# cryptostick-0v3.net
KiCad netlist of a schematic drawn in EAGLE
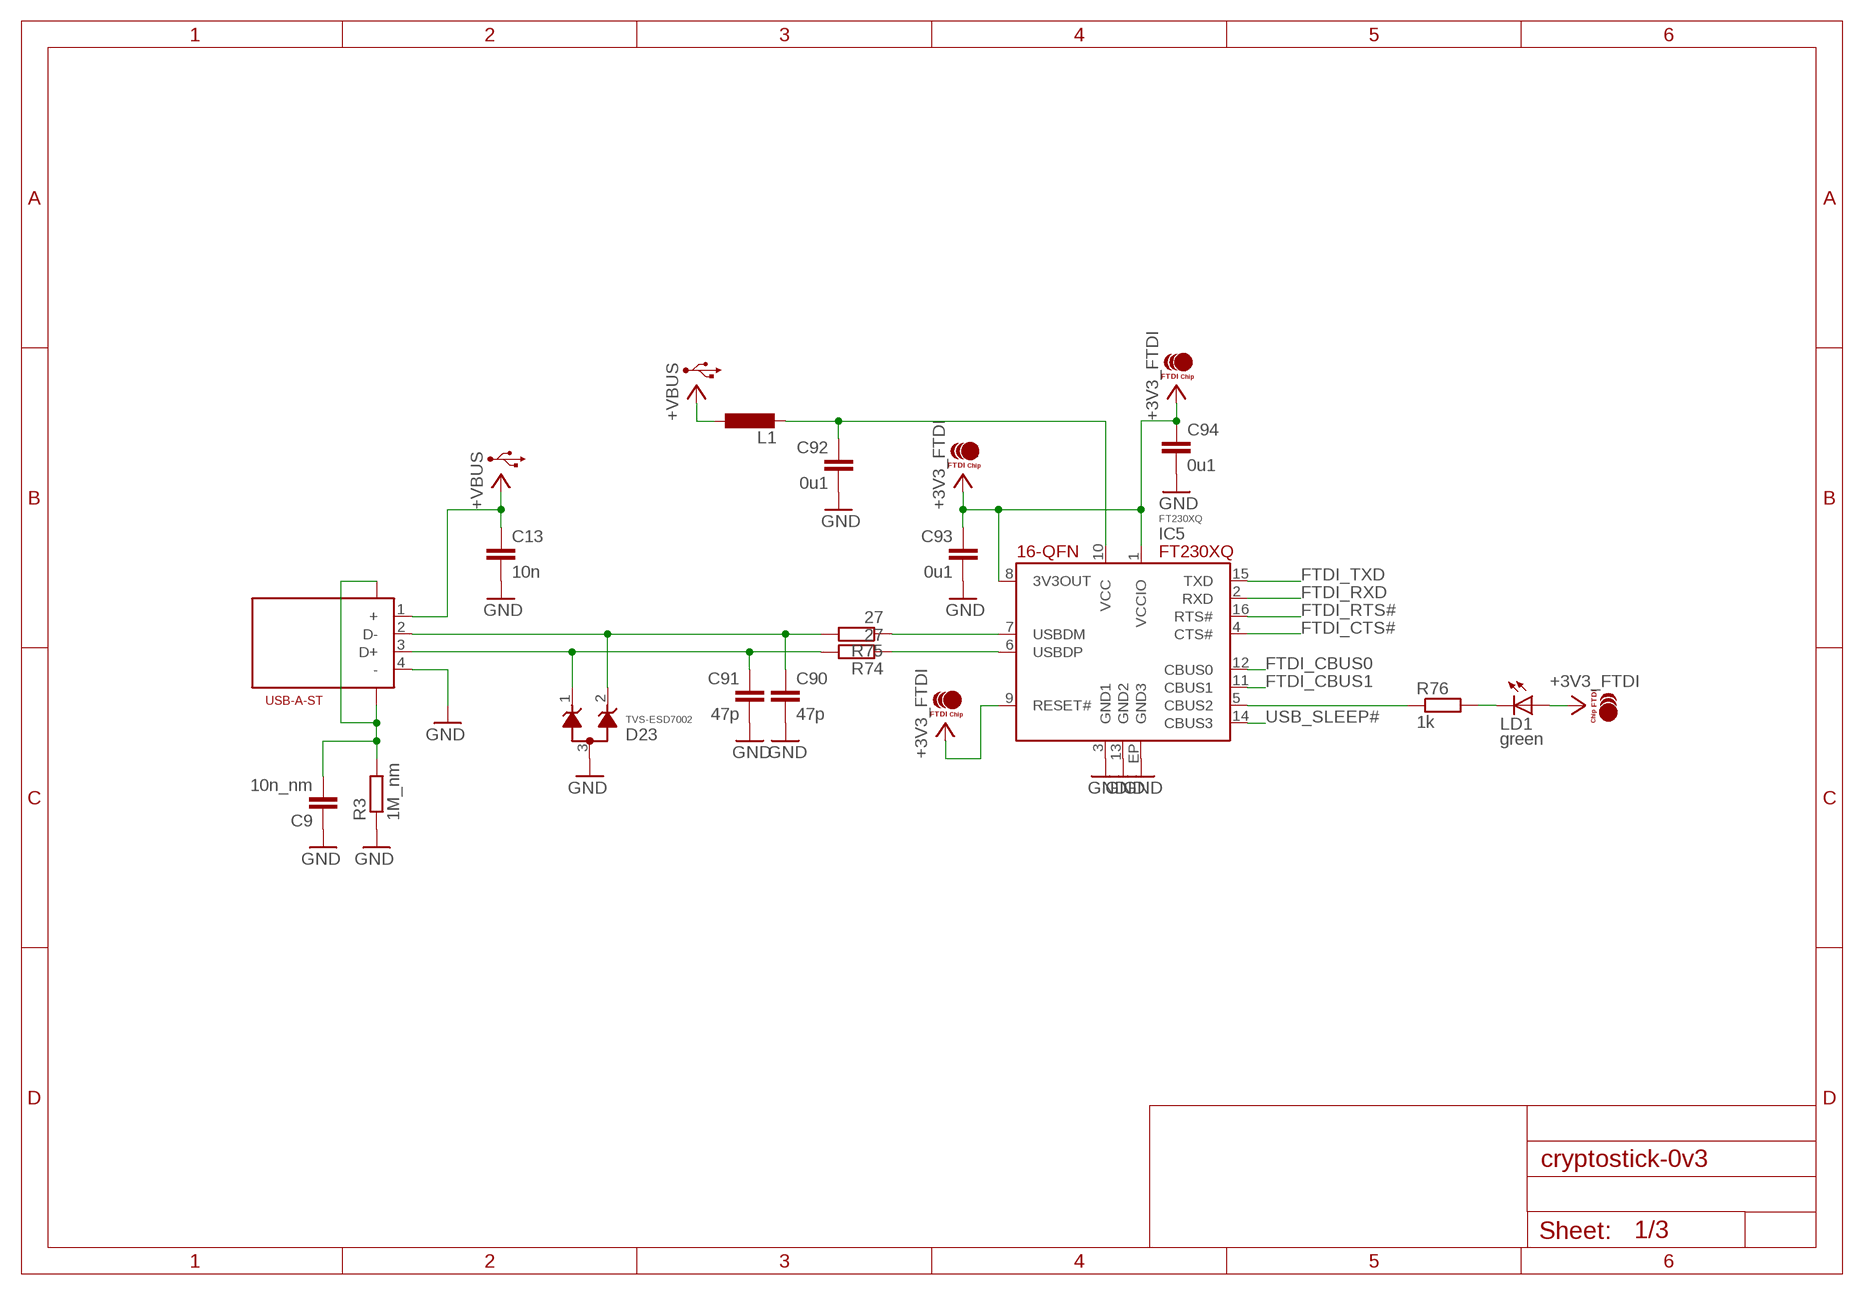
[diagram p0: schematic, sheet 1]
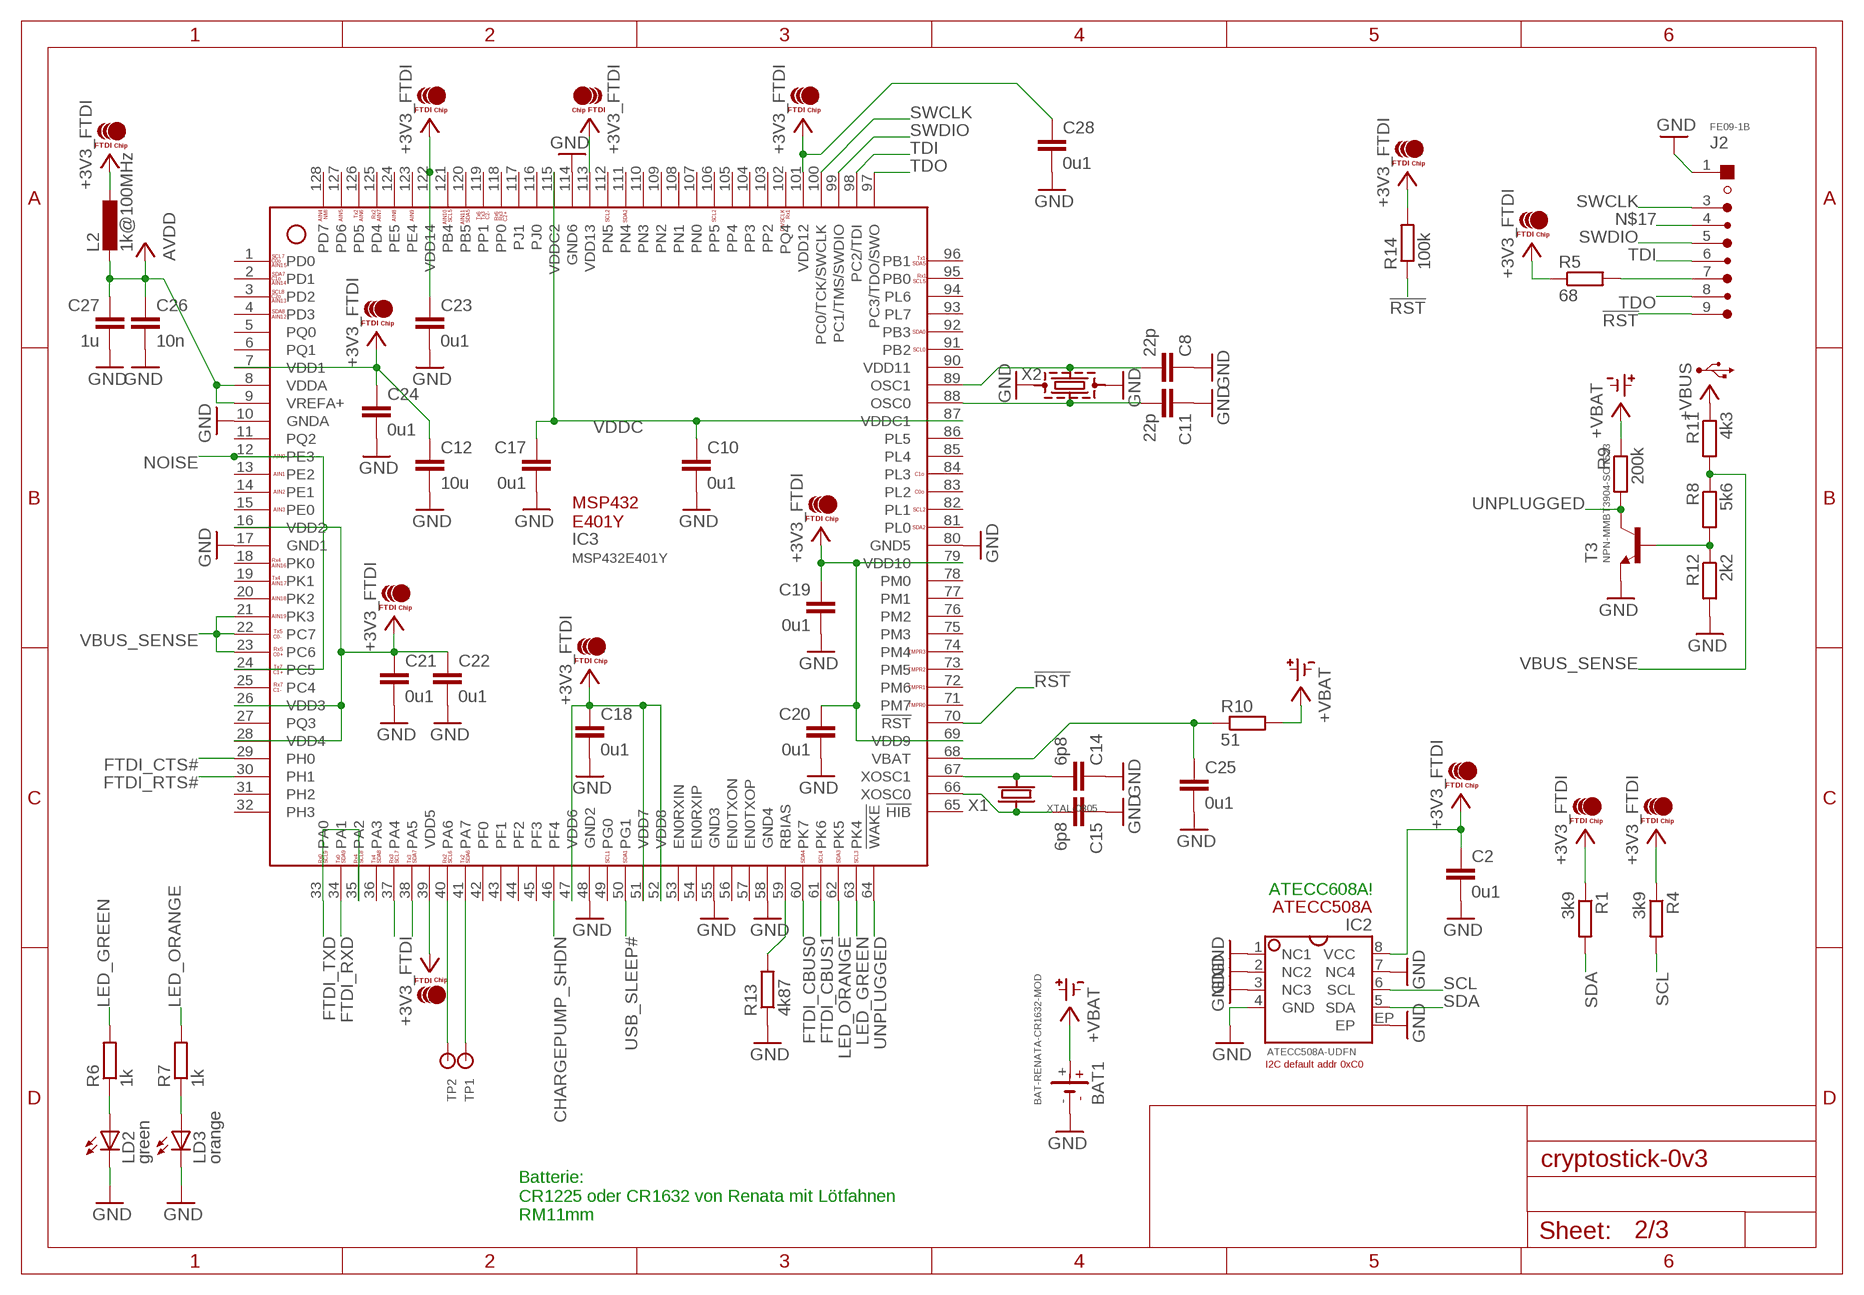
[diagram p1: schematic, sheet 2]
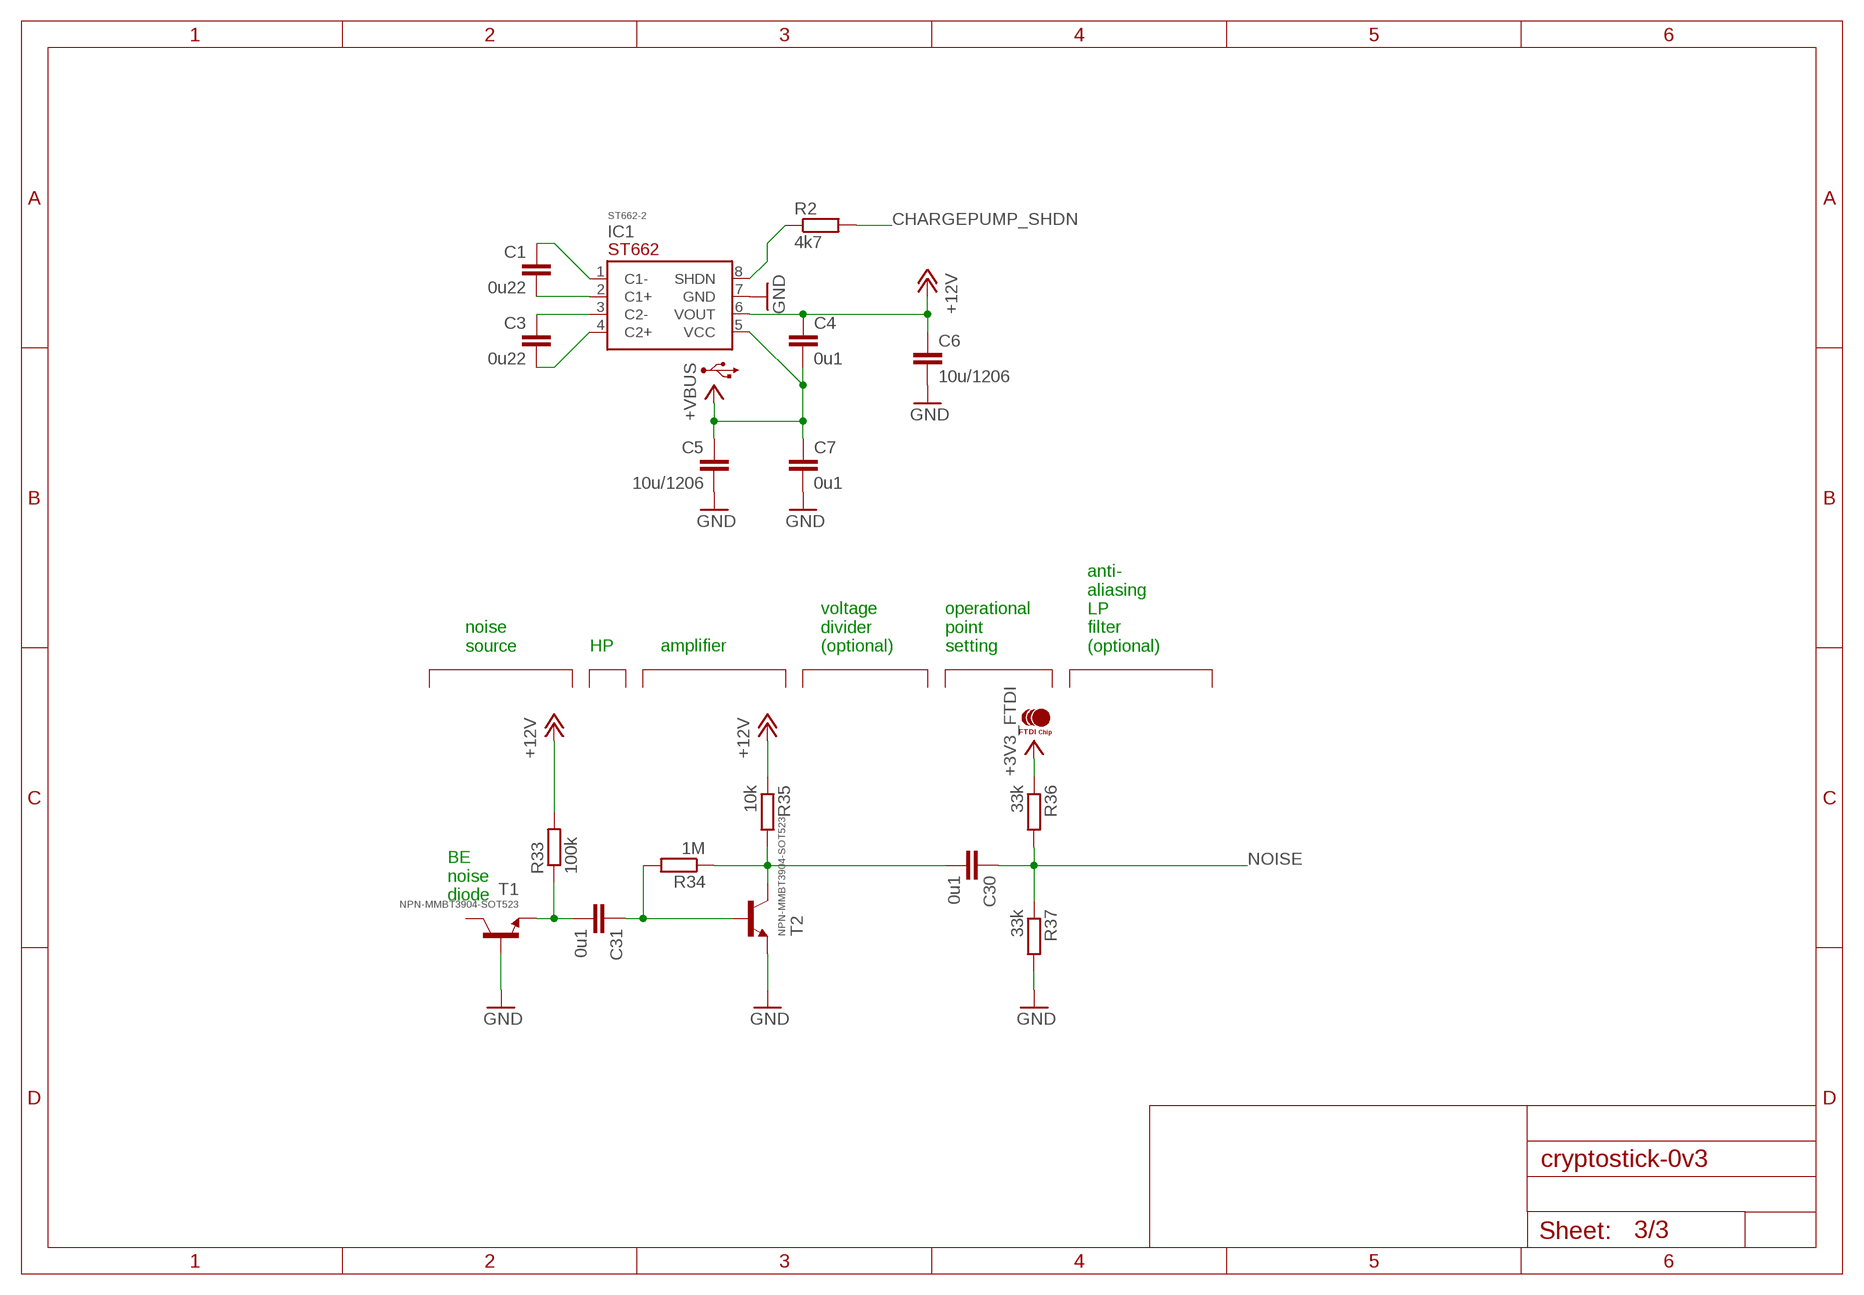
[diagram p2: schematic, sheet 3]

(export (version "E")
  (design (tool "Eeschema 10.0.6"))
  (components
    (comp (ref "C9")
      (value "10n_nm")
      (footprint "eagle-import:C0603")
      (libsource (lib "eagle-import") (part "C-EUC0603"))
    )
    (comp (ref "C13")
      (value "10n")
      (footprint "eagle-import:R0402-MCU")
      (libsource (lib "eagle-import") (part "C-EUR0402-MCU"))
    )
    (comp (ref "C90")
      (value "47p")
      (footprint "eagle-import:R0402-MCU")
      (libsource (lib "eagle-import") (part "C-EUR0402-MCU"))
    )
    (comp (ref "C91")
      (value "47p")
      (footprint "eagle-import:R0402-MCU")
      (libsource (lib "eagle-import") (part "C-EUR0402-MCU"))
    )
    (comp (ref "C92")
      (value "0u1")
      (footprint "eagle-import:R0402-MCU")
      (libsource (lib "eagle-import") (part "C-EUR0402-MCU"))
    )
    (comp (ref "C93")
      (value "0u1")
      (footprint "eagle-import:R0402-MCU")
      (libsource (lib "eagle-import") (part "C-EUR0402-MCU"))
    )
    (comp (ref "C94")
      (value "0u1")
      (footprint "eagle-import:R0402-MCU")
      (libsource (lib "eagle-import") (part "C-EUR0402-MCU"))
    )
    (comp (ref "D23")
      (value "TVS-ESD7002")
      (footprint "eagle-import:SC70-3")
      (libsource (lib "eagle-import") (part "TVS-ESD7002"))
    )
    (comp (ref "IC5")
      (value "FT230XQ")
      (footprint "eagle-import:16QFN-FT230X")
      (libsource (lib "eagle-import") (part "FT230XQ"))
    )
    (comp (ref "J1")
      (value "USB-A-ST")
      (footprint "eagle-import:USB-A-ST")
      (libsource (lib "eagle-import") (part "USB-A-ST"))
    )
    (comp (ref "L1")
      (value "L-EUR0402-MCU")
      (footprint "eagle-import:R0402-MCU")
      (libsource (lib "eagle-import") (part "L-EUR0402-MCU"))
    )
    (comp (ref "LD1")
      (value "green")
      (footprint "eagle-import:0603-SIDELED-RPI")
      (libsource (lib "eagle-import") (part "LED-0603-SIDELED-RPI"))
    )
    (comp (ref "R3")
      (value "1M_nm")
      (footprint "eagle-import:R0603")
      (libsource (lib "eagle-import") (part "R-EU_R0603"))
    )
    (comp (ref "R74")
      (value "27")
      (footprint "eagle-import:R0402-MCU")
      (libsource (lib "eagle-import") (part "R-EU_R0402-MCU"))
    )
    (comp (ref "R75")
      (value "27")
      (footprint "eagle-import:R0402-MCU")
      (libsource (lib "eagle-import") (part "R-EU_R0402-MCU"))
    )
    (comp (ref "R76")
      (value "1k")
      (footprint "eagle-import:R0402-MCU")
      (libsource (lib "eagle-import") (part "R-EU_R0402-MCU"))
    )
    (comp (ref "C1")
      (value "0u22")
      (footprint "eagle-import:C0603")
      (libsource (lib "eagle-import") (part "C-EUC0603"))
    )
    (comp (ref "C3")
      (value "0u22")
      (footprint "eagle-import:C0603")
      (libsource (lib "eagle-import") (part "C-EUC0603"))
    )
    (comp (ref "C4")
      (value "0u1")
      (footprint "eagle-import:R0402-MCU")
      (libsource (lib "eagle-import") (part "C-EUR0402-MCU"))
    )
    (comp (ref "C5")
      (value "10u/1206")
      (footprint "eagle-import:C1206")
      (libsource (lib "eagle-import") (part "C-EUC1206"))
    )
    (comp (ref "C6")
      (value "10u/1206")
      (footprint "eagle-import:C1206")
      (libsource (lib "eagle-import") (part "C-EUC1206"))
    )
    (comp (ref "C7")
      (value "0u1")
      (footprint "eagle-import:R0402-MCU")
      (libsource (lib "eagle-import") (part "C-EUR0402-MCU"))
    )
    (comp (ref "C30")
      (value "0u1")
      (footprint "eagle-import:R0402-MCU")
      (libsource (lib "eagle-import") (part "C-EUR0402-MCU"))
    )
    (comp (ref "C31")
      (value "0u1")
      (footprint "eagle-import:R0402-MCU")
      (libsource (lib "eagle-import") (part "C-EUR0402-MCU"))
    )
    (comp (ref "IC1")
      (value "ST662-2")
      (footprint "eagle-import:8SOIC-2")
      (libsource (lib "eagle-import") (part "ST662-2"))
    )
    (comp (ref "R2")
      (value "4k7")
      (footprint "eagle-import:R0402-MCU")
      (libsource (lib "eagle-import") (part "R-EU_R0402-MCU"))
    )
    (comp (ref "R33")
      (value "100k")
      (footprint "eagle-import:R0402-MCU")
      (libsource (lib "eagle-import") (part "R-EU_R0402-MCU"))
    )
    (comp (ref "R34")
      (value "1M")
      (footprint "eagle-import:R0402-MCU")
      (libsource (lib "eagle-import") (part "R-EU_R0402-MCU"))
    )
    (comp (ref "R35")
      (value "10k")
      (footprint "eagle-import:R0402-MCU")
      (libsource (lib "eagle-import") (part "R-EU_R0402-MCU"))
    )
    (comp (ref "R36")
      (value "33k")
      (footprint "eagle-import:R0402-MCU")
      (libsource (lib "eagle-import") (part "R-EU_R0402-MCU"))
    )
    (comp (ref "R37")
      (value "33k")
      (footprint "eagle-import:R0402-MCU")
      (libsource (lib "eagle-import") (part "R-EU_R0402-MCU"))
    )
    (comp (ref "T1")
      (value "NPN-MMBT3904-SOT523")
      (footprint "eagle-import:SOT523")
      (libsource (lib "eagle-import") (part "NPN-MMBT3904-SOT523"))
    )
    (comp (ref "T2")
      (value "NPN-MMBT3904-SOT523")
      (footprint "eagle-import:SOT523")
      (libsource (lib "eagle-import") (part "NPN-MMBT3904-SOT523"))
    )
    (comp (ref "BAT1")
      (value "BAT-RENATA-CR1632-MOD")
      (footprint "eagle-import:BAT-RENATA-CR1632-MOD")
      (libsource (lib "eagle-import") (part "BAT-RENATA-CR1632-MOD"))
    )
    (comp (ref "C2")
      (value "0u1")
      (footprint "eagle-import:R0402-MCU")
      (libsource (lib "eagle-import") (part "C-EUR0402-MCU"))
    )
    (comp (ref "C8")
      (value "22p")
      (footprint "eagle-import:R0402-MCU")
      (libsource (lib "eagle-import") (part "C-EUR0402-MCU"))
    )
    (comp (ref "C10")
      (value "0u1")
      (footprint "eagle-import:R0402-MCU")
      (libsource (lib "eagle-import") (part "C-EUR0402-MCU"))
    )
    (comp (ref "C11")
      (value "22p")
      (footprint "eagle-import:R0402-MCU")
      (libsource (lib "eagle-import") (part "C-EUR0402-MCU"))
    )
    (comp (ref "C12")
      (value "10u")
      (footprint "eagle-import:R0603-MCU")
      (libsource (lib "eagle-import") (part "C-EUR0603-MCU"))
    )
    (comp (ref "C14")
      (value "6p8")
      (footprint "eagle-import:R0402-MCU")
      (libsource (lib "eagle-import") (part "C-EUR0402-MCU"))
    )
    (comp (ref "C15")
      (value "6p8")
      (footprint "eagle-import:R0402-MCU")
      (libsource (lib "eagle-import") (part "C-EUR0402-MCU"))
    )
    (comp (ref "C17")
      (value "0u1")
      (footprint "eagle-import:R0402-MCU")
      (libsource (lib "eagle-import") (part "C-EUR0402-MCU"))
    )
    (comp (ref "C18")
      (value "0u1")
      (footprint "eagle-import:R0402-MCU")
      (libsource (lib "eagle-import") (part "C-EUR0402-MCU"))
    )
    (comp (ref "C19")
      (value "0u1")
      (footprint "eagle-import:R0402-MCU")
      (libsource (lib "eagle-import") (part "C-EUR0402-MCU"))
    )
    (comp (ref "C20")
      (value "0u1")
      (footprint "eagle-import:R0402-MCU")
      (libsource (lib "eagle-import") (part "C-EUR0402-MCU"))
    )
    (comp (ref "C21")
      (value "0u1")
      (footprint "eagle-import:R0402-MCU")
      (libsource (lib "eagle-import") (part "C-EUR0402-MCU"))
    )
    (comp (ref "C22")
      (value "0u1")
      (footprint "eagle-import:R0402-MCU")
      (libsource (lib "eagle-import") (part "C-EUR0402-MCU"))
    )
    (comp (ref "C23")
      (value "0u1")
      (footprint "eagle-import:R0402-MCU")
      (libsource (lib "eagle-import") (part "C-EUR0402-MCU"))
    )
    (comp (ref "C24")
      (value "0u1")
      (footprint "eagle-import:R0402-MCU")
      (libsource (lib "eagle-import") (part "C-EUR0402-MCU"))
    )
    (comp (ref "C25")
      (value "0u1")
      (footprint "eagle-import:R0402-MCU")
      (libsource (lib "eagle-import") (part "C-EUR0402-MCU"))
    )
    (comp (ref "C26")
      (value "10n")
      (footprint "eagle-import:R0402-MCU")
      (libsource (lib "eagle-import") (part "C-EUR0402-MCU"))
    )
    (comp (ref "C27")
      (value "1u")
      (footprint "eagle-import:R0402-MCU")
      (libsource (lib "eagle-import") (part "C-EUR0402-MCU"))
    )
    (comp (ref "C28")
      (value "0u1")
      (footprint "eagle-import:R0402-MCU")
      (libsource (lib "eagle-import") (part "C-EUR0402-MCU"))
    )
    (comp (ref "IC2")
      (value "ATECC508A-UDFN")
      (footprint "eagle-import:8UDFN")
      (libsource (lib "eagle-import") (part "ATECC508A-UDFN"))
    )
    (comp (ref "IC3")
      (value "MSP432E401Y")
      (footprint "eagle-import:128TQFP-MSP432E401Y")
      (libsource (lib "eagle-import") (part "MSP432E401Y"))
    )
    (comp (ref "J2")
      (value "FE09-1B")
      (footprint "eagle-import:FE09-1B")
      (libsource (lib "eagle-import") (part "FE09-1B"))
    )
    (comp (ref "L2")
      (value "1k@100MHz")
      (footprint "eagle-import:R0402-MCU")
      (libsource (lib "eagle-import") (part "L-EUR0402-MCU"))
    )
    (comp (ref "LD2")
      (value "green")
      (footprint "eagle-import:0603-SIDELED-RPI")
      (libsource (lib "eagle-import") (part "LED-0603-SIDELED-RPI"))
    )
    (comp (ref "LD3")
      (value "orange")
      (footprint "eagle-import:0603-SIDELED-RPI")
      (libsource (lib "eagle-import") (part "LED-0603-SIDELED-RPI"))
    )
    (comp (ref "R1")
      (value "3k9")
      (footprint "eagle-import:R0402-MCU")
      (libsource (lib "eagle-import") (part "R-EU_R0402-MCU"))
    )
    (comp (ref "R4")
      (value "3k9")
      (footprint "eagle-import:R0402-MCU")
      (libsource (lib "eagle-import") (part "R-EU_R0402-MCU"))
    )
    (comp (ref "R5")
      (value "68")
      (footprint "eagle-import:R0402-MCU")
      (libsource (lib "eagle-import") (part "R-EU_R0402-MCU"))
    )
    (comp (ref "R6")
      (value "1k")
      (footprint "eagle-import:R0402-MCU")
      (libsource (lib "eagle-import") (part "R-EU_R0402-MCU"))
    )
    (comp (ref "R7")
      (value "1k")
      (footprint "eagle-import:R0402-MCU")
      (libsource (lib "eagle-import") (part "R-EU_R0402-MCU"))
    )
    (comp (ref "R8")
      (value "5k6")
      (footprint "eagle-import:R0402-MCU")
      (libsource (lib "eagle-import") (part "R-EU_R0402-MCU"))
    )
    (comp (ref "R9")
      (value "200k")
      (footprint "eagle-import:R0402-MCU")
      (libsource (lib "eagle-import") (part "R-EU_R0402-MCU"))
    )
    (comp (ref "R10")
      (value "51")
      (footprint "eagle-import:R0402-MCU")
      (libsource (lib "eagle-import") (part "R-EU_R0402-MCU"))
    )
    (comp (ref "R11")
      (value "4k3")
      (footprint "eagle-import:R0402-MCU")
      (libsource (lib "eagle-import") (part "R-EU_R0402-MCU"))
    )
    (comp (ref "R12")
      (value "2k2")
      (footprint "eagle-import:R0402-MCU")
      (libsource (lib "eagle-import") (part "R-EU_R0402-MCU"))
    )
    (comp (ref "R13")
      (value "4k87")
      (footprint "eagle-import:R0402-MCU")
      (libsource (lib "eagle-import") (part "R-EU_R0402-MCU"))
    )
    (comp (ref "R14")
      (value "100k")
      (footprint "eagle-import:R0402-MCU")
      (libsource (lib "eagle-import") (part "R-EU_R0402-MCU"))
    )
    (comp (ref "T3")
      (value "NPN-MMBT3904-SOT523")
      (footprint "eagle-import:SOT523")
      (libsource (lib "eagle-import") (part "NPN-MMBT3904-SOT523"))
    )
    (comp (ref "TP1")
      (value "TP-SMT-1.5MM")
      (footprint "eagle-import:TP-SMT-1.5MM")
      (libsource (lib "eagle-import") (part "TP-SMT-1.5MM"))
    )
    (comp (ref "TP2")
      (value "TP-SMT-1.5MM")
      (footprint "eagle-import:TP-SMT-1.5MM")
      (libsource (lib "eagle-import") (part "TP-SMT-1.5MM"))
    )
    (comp (ref "X1")
      (value "XTAL-0805")
      (footprint "eagle-import:XTAL-32KHZ-0805")
      (libsource (lib "eagle-import") (part "XTAL-0805"))
    )
    (comp (ref "X2")
      (value "XTAL-2.0X1.6-MOD")
      (footprint "eagle-import:XTAL-2.0X1.6-MOD")
      (libsource (lib "eagle-import") (part "XTAL-2.0X1.6-MOD"))
    )
  )
  (nets
    (net (code "1") (name "+3V3_FTDI") (class "Default")
      (node (ref "C12") (pin "1") (pinfunction "1_1") (pintype "passive"))
      (node (ref "C18") (pin "1") (pinfunction "1_1") (pintype "passive"))
      (node (ref "C19") (pin "1") (pinfunction "1_1") (pintype "passive"))
      (node (ref "C2") (pin "1") (pinfunction "1_1") (pintype "passive"))
      (node (ref "C20") (pin "1") (pinfunction "1_1") (pintype "passive"))
      (node (ref "C21") (pin "1") (pinfunction "1_1") (pintype "passive"))
      (node (ref "C22") (pin "1") (pinfunction "1_1") (pintype "passive"))
      (node (ref "C23") (pin "1") (pinfunction "1_1") (pintype "passive"))
      (node (ref "C24") (pin "1") (pinfunction "1_1") (pintype "passive"))
      (node (ref "C28") (pin "1") (pinfunction "1_1") (pintype "passive"))
      (node (ref "C93") (pin "1") (pinfunction "1_1") (pintype "passive"))
      (node (ref "C94") (pin "1") (pinfunction "1_1") (pintype "passive"))
      (node (ref "IC2") (pin "8") (pinfunction "VCC_8") (pintype "bidirectional"))
      (node (ref "IC3") (pin "101") (pinfunction "VDD12_101") (pintype "bidirectional"))
      (node (ref "IC3") (pin "113") (pinfunction "VDD13_113") (pintype "bidirectional"))
      (node (ref "IC3") (pin "122") (pinfunction "VDD14_122") (pintype "bidirectional"))
      (node (ref "IC3") (pin "16") (pinfunction "VDD2_16") (pintype "bidirectional"))
      (node (ref "IC3") (pin "26") (pinfunction "VDD3_26") (pintype "bidirectional"))
      (node (ref "IC3") (pin "28") (pinfunction "VDD4_28") (pintype "bidirectional"))
      (node (ref "IC3") (pin "39") (pinfunction "VDD5_39") (pintype "bidirectional"))
      (node (ref "IC3") (pin "47") (pinfunction "VDD6_47") (pintype "bidirectional"))
      (node (ref "IC3") (pin "51") (pinfunction "VDD7_51") (pintype "bidirectional"))
      (node (ref "IC3") (pin "52") (pinfunction "VDD8_52") (pintype "bidirectional"))
      (node (ref "IC3") (pin "69") (pinfunction "VDD9_69") (pintype "bidirectional"))
      (node (ref "IC3") (pin "7") (pinfunction "VDD1_7") (pintype "bidirectional"))
      (node (ref "IC3") (pin "79") (pinfunction "VDD10_79") (pintype "bidirectional"))
      (node (ref "IC5") (pin "1") (pinfunction "VCCIO_1") (pintype "bidirectional"))
      (node (ref "IC5") (pin "8") (pinfunction "3V3OUT_8") (pintype "bidirectional"))
      (node (ref "IC5") (pin "9") (pinfunction "RESET#_9") (pintype "bidirectional"))
      (node (ref "L2") (pin "1") (pinfunction "1_1") (pintype "passive"))
      (node (ref "LD1") (pin "A") (pinfunction "A_A") (pintype "passive"))
      (node (ref "R1") (pin "1") (pinfunction "1_1") (pintype "passive"))
      (node (ref "R14") (pin "2") (pinfunction "2_2") (pintype "passive"))
      (node (ref "R36") (pin "1") (pinfunction "1_1") (pintype "passive"))
      (node (ref "R4") (pin "1") (pinfunction "1_1") (pintype "passive"))
      (node (ref "R5") (pin "1") (pinfunction "1_1") (pintype "passive"))
    )
    (net (code "2") (name "+12V") (class "Default")
      (node (ref "C4") (pin "1") (pinfunction "1_1") (pintype "passive"))
      (node (ref "C6") (pin "1") (pinfunction "1_1") (pintype "passive"))
      (node (ref "IC1") (pin "6") (pinfunction "VOUT_6") (pintype "bidirectional"))
      (node (ref "R33") (pin "2") (pinfunction "2_2") (pintype "passive"))
      (node (ref "R35") (pin "1") (pinfunction "1_1") (pintype "passive"))
    )
    (net (code "3") (name "+VBAT") (class "Default")
      (node (ref "BAT1") (pin "+") (pinfunction "+_+") (pintype "bidirectional"))
      (node (ref "R10") (pin "2") (pinfunction "2_2") (pintype "passive"))
      (node (ref "R9") (pin "1") (pinfunction "1_1") (pintype "passive"))
    )
    (net (code "4") (name "+VBUS") (class "Default")
      (node (ref "C13") (pin "1") (pinfunction "1_1") (pintype "passive"))
      (node (ref "C4") (pin "2") (pinfunction "2_2") (pintype "passive"))
      (node (ref "C5") (pin "1") (pinfunction "1_1") (pintype "passive"))
      (node (ref "C7") (pin "1") (pinfunction "1_1") (pintype "passive"))
      (node (ref "IC1") (pin "5") (pinfunction "VCC_5") (pintype "bidirectional"))
      (node (ref "J1") (pin "1") (pinfunction "+_1") (pintype "bidirectional"))
      (node (ref "L1") (pin "1") (pinfunction "1_1") (pintype "passive"))
      (node (ref "R11") (pin "1") (pinfunction "1_1") (pintype "passive"))
    )
    (net (code "5") (name "AVDD") (class "Default")
      (node (ref "C26") (pin "1") (pinfunction "1_1") (pintype "passive"))
      (node (ref "C27") (pin "1") (pinfunction "1_1") (pintype "passive"))
      (node (ref "IC3") (pin "8") (pinfunction "VDDA_8") (pintype "bidirectional"))
      (node (ref "IC3") (pin "9") (pinfunction "VREFA+_9") (pintype "bidirectional"))
      (node (ref "L2") (pin "2") (pinfunction "2_2") (pintype "passive"))
    )
    (net (code "6") (name "CHARGEPUMP_SHDN") (class "Default")
      (node (ref "IC3") (pin "46") (pinfunction "PF4_46") (pintype "bidirectional"))
      (node (ref "R2") (pin "2") (pinfunction "2_2") (pintype "passive"))
    )
    (net (code "7") (name "DBG_RXD") (class "Default")
      (node (ref "IC3") (pin "40") (pinfunction "PA6_40") (pintype "bidirectional"))
      (node (ref "IC3") (pin "74") (pinfunction "PM4_74") (pintype "bidirectional"))
      (node (ref "TP2") (pin "1") (pinfunction "1_1") (pintype "bidirectional"))
    )
    (net (code "8") (name "DBG_TXD") (class "Default")
      (node (ref "IC3") (pin "41") (pinfunction "PA7_41") (pintype "bidirectional"))
      (node (ref "IC3") (pin "73") (pinfunction "PM5_73") (pintype "bidirectional"))
      (node (ref "TP1") (pin "1") (pinfunction "1_1") (pintype "bidirectional"))
    )
    (net (code "9") (name "FTDI_CBUS0") (class "Default")
      (node (ref "IC3") (pin "60") (pinfunction "PK7_60") (pintype "bidirectional"))
      (node (ref "IC5") (pin "12") (pinfunction "CBUS0_12") (pintype "bidirectional"))
    )
    (net (code "10") (name "FTDI_CBUS1") (class "Default")
      (node (ref "IC3") (pin "61") (pinfunction "PK6_61") (pintype "bidirectional"))
      (node (ref "IC5") (pin "11") (pinfunction "CBUS1_11") (pintype "bidirectional"))
    )
    (net (code "11") (name "FTDI_CTS#") (class "Default")
      (node (ref "IC3") (pin "29") (pinfunction "PH0_29") (pintype "bidirectional"))
      (node (ref "IC5") (pin "4") (pinfunction "CTS#_4") (pintype "bidirectional"))
    )
    (net (code "12") (name "FTDI_RTS#") (class "Default")
      (node (ref "IC3") (pin "30") (pinfunction "PH1_30") (pintype "bidirectional"))
      (node (ref "IC5") (pin "16") (pinfunction "RTS#_16") (pintype "bidirectional"))
    )
    (net (code "13") (name "FTDI_RXD") (class "Default")
      (node (ref "IC3") (pin "34") (pinfunction "PA1_34") (pintype "bidirectional"))
      (node (ref "IC5") (pin "2") (pinfunction "RXD_2") (pintype "bidirectional"))
    )
    (net (code "14") (name "FTDI_TXD") (class "Default")
      (node (ref "IC3") (pin "33") (pinfunction "PA0_33") (pintype "bidirectional"))
      (node (ref "IC3") (pin "35") (pinfunction "PA2_35") (pintype "bidirectional"))
      (node (ref "IC5") (pin "15") (pinfunction "TXD_15") (pintype "bidirectional"))
    )
    (net (code "15") (name "GND") (class "Default")
      (node (ref "BAT1") (pin "-") (pinfunction "-_-") (pintype "bidirectional"))
      (node (ref "C10") (pin "2") (pinfunction "2_2") (pintype "passive"))
      (node (ref "C11") (pin "1") (pinfunction "1_1") (pintype "passive"))
      (node (ref "C12") (pin "2") (pinfunction "2_2") (pintype "passive"))
      (node (ref "C13") (pin "2") (pinfunction "2_2") (pintype "passive"))
      (node (ref "C14") (pin "1") (pinfunction "1_1") (pintype "passive"))
      (node (ref "C15") (pin "1") (pinfunction "1_1") (pintype "passive"))
      (node (ref "C17") (pin "2") (pinfunction "2_2") (pintype "passive"))
      (node (ref "C18") (pin "2") (pinfunction "2_2") (pintype "passive"))
      (node (ref "C19") (pin "2") (pinfunction "2_2") (pintype "passive"))
      (node (ref "C2") (pin "2") (pinfunction "2_2") (pintype "passive"))
      (node (ref "C20") (pin "2") (pinfunction "2_2") (pintype "passive"))
      (node (ref "C21") (pin "2") (pinfunction "2_2") (pintype "passive"))
      (node (ref "C22") (pin "2") (pinfunction "2_2") (pintype "passive"))
      (node (ref "C23") (pin "2") (pinfunction "2_2") (pintype "passive"))
      (node (ref "C24") (pin "2") (pinfunction "2_2") (pintype "passive"))
      (node (ref "C25") (pin "2") (pinfunction "2_2") (pintype "passive"))
      (node (ref "C26") (pin "2") (pinfunction "2_2") (pintype "passive"))
      (node (ref "C27") (pin "2") (pinfunction "2_2") (pintype "passive"))
      (node (ref "C28") (pin "2") (pinfunction "2_2") (pintype "passive"))
      (node (ref "C5") (pin "2") (pinfunction "2_2") (pintype "passive"))
      (node (ref "C6") (pin "2") (pinfunction "2_2") (pintype "passive"))
      (node (ref "C7") (pin "2") (pinfunction "2_2") (pintype "passive"))
      (node (ref "C8") (pin "1") (pinfunction "1_1") (pintype "passive"))
      (node (ref "C9") (pin "1") (pinfunction "1_1") (pintype "passive"))
      (node (ref "C90") (pin "2") (pinfunction "2_2") (pintype "passive"))
      (node (ref "C91") (pin "2") (pinfunction "2_2") (pintype "passive"))
      (node (ref "C92") (pin "2") (pinfunction "2_2") (pintype "passive"))
      (node (ref "C93") (pin "2") (pinfunction "2_2") (pintype "passive"))
      (node (ref "C94") (pin "2") (pinfunction "2_2") (pintype "passive"))
      (node (ref "D23") (pin "3") (pinfunction "3_3") (pintype "bidirectional"))
      (node (ref "IC1") (pin "7") (pinfunction "GND_7") (pintype "bidirectional"))
      (node (ref "IC2") (pin "1") (pinfunction "NC1_1") (pintype "bidirectional"))
      (node (ref "IC2") (pin "2") (pinfunction "NC2_2") (pintype "bidirectional"))
      (node (ref "IC2") (pin "3") (pinfunction "NC3_3") (pintype "bidirectional"))
      (node (ref "IC2") (pin "4") (pinfunction "GND_4") (pintype "bidirectional"))
      (node (ref "IC2") (pin "7") (pinfunction "NC4_7") (pintype "bidirectional"))
      (node (ref "IC2") (pin "EP") (pinfunction "EP_EP") (pintype "bidirectional"))
      (node (ref "IC3") (pin "10") (pinfunction "GNDA_10") (pintype "bidirectional"))
      (node (ref "IC3") (pin "114") (pinfunction "GND6_114") (pintype "bidirectional"))
      (node (ref "IC3") (pin "17") (pinfunction "GND1_17") (pintype "bidirectional"))
      (node (ref "IC3") (pin "48") (pinfunction "GND2_48") (pintype "bidirectional"))
      (node (ref "IC3") (pin "55") (pinfunction "GND3_55") (pintype "bidirectional"))
      (node (ref "IC3") (pin "58") (pinfunction "GND4_58") (pintype "bidirectional"))
      (node (ref "IC3") (pin "80") (pinfunction "GND5_80") (pintype "bidirectional"))
      (node (ref "IC5") (pin "13") (pinfunction "GND2_13") (pintype "bidirectional"))
      (node (ref "IC5") (pin "3") (pinfunction "GND1_3") (pintype "bidirectional"))
      (node (ref "IC5") (pin "EP") (pinfunction "GND3_EP") (pintype "bidirectional"))
      (node (ref "J1") (pin "4") (pinfunction "-_4") (pintype "bidirectional"))
      (node (ref "J2") (pin "1") (pinfunction "1_1") (pintype "bidirectional"))
      (node (ref "LD2") (pin "C") (pinfunction "C_C") (pintype "passive"))
      (node (ref "LD3") (pin "C") (pinfunction "C_C") (pintype "passive"))
      (node (ref "R12") (pin "2") (pinfunction "2_2") (pintype "passive"))
      (node (ref "R13") (pin "1") (pinfunction "1_1") (pintype "passive"))
      (node (ref "R3") (pin "1") (pinfunction "1_1") (pintype "passive"))
      (node (ref "R37") (pin "2") (pinfunction "2_2") (pintype "passive"))
      (node (ref "T1") (pin "1") (pinfunction "B_1") (pintype "passive"))
      (node (ref "T2") (pin "2") (pinfunction "E_2") (pintype "passive"))
      (node (ref "T3") (pin "2") (pinfunction "E_2") (pintype "passive"))
      (node (ref "X2") (pin "2") (pinfunction "GND1_2") (pintype "bidirectional"))
      (node (ref "X2") (pin "4") (pinfunction "GND2_4") (pintype "bidirectional"))
    )
    (net (code "16") (name "LED_GREEN") (class "Default")
      (node (ref "IC3") (pin "63") (pinfunction "PK4_63") (pintype "bidirectional"))
      (node (ref "R6") (pin "2") (pinfunction "2_2") (pintype "passive"))
    )
    (net (code "17") (name "LED_ORANGE") (class "Default")
      (node (ref "IC3") (pin "62") (pinfunction "PK5_62") (pintype "bidirectional"))
      (node (ref "R7") (pin "2") (pinfunction "2_2") (pintype "passive"))
    )
    (net (code "18") (name "N$17") (class "Default")
      (node (ref "J2") (pin "4") (pinfunction "4_4") (pintype "bidirectional"))
    )
    (net (code "19") (name "NOISE") (class "Default")
      (node (ref "C30") (pin "1") (pinfunction "1_1") (pintype "passive"))
      (node (ref "IC3") (pin "12") (pinfunction "PE3_12") (pintype "bidirectional"))
      (node (ref "IC3") (pin "24") (pinfunction "PC5_24") (pintype "bidirectional"))
      (node (ref "R36") (pin "2") (pinfunction "2_2") (pintype "passive"))
      (node (ref "R37") (pin "1") (pinfunction "1_1") (pintype "passive"))
    )
    (net (code "20") (name "Net-(C9-Pad2)") (class "Default")
      (node (ref "C9") (pin "2") (pinfunction "2_2") (pintype "passive"))
      (node (ref "J1") (pin "SH1") (pinfunction "SH1_SH1") (pintype "bidirectional"))
      (node (ref "J1") (pin "SH2") (pinfunction "SH2_SH2") (pintype "bidirectional"))
      (node (ref "R3") (pin "2") (pinfunction "2_2") (pintype "passive"))
    )
    (net (code "21") (name "Net-(IC1-C1+)") (class "Default")
      (node (ref "C1") (pin "2") (pinfunction "2_2") (pintype "passive"))
      (node (ref "IC1") (pin "2") (pinfunction "C1+_2") (pintype "bidirectional"))
    )
    (net (code "22") (name "Net-(IC1-C1-)") (class "Default")
      (node (ref "C1") (pin "1") (pinfunction "1_1") (pintype "passive"))
      (node (ref "IC1") (pin "1") (pinfunction "C1-_1") (pintype "bidirectional"))
    )
    (net (code "23") (name "Net-(IC1-C2+)") (class "Default")
      (node (ref "C3") (pin "2") (pinfunction "2_2") (pintype "passive"))
      (node (ref "IC1") (pin "4") (pinfunction "C2+_4") (pintype "bidirectional"))
    )
    (net (code "24") (name "Net-(IC1-C2-)") (class "Default")
      (node (ref "C3") (pin "1") (pinfunction "1_1") (pintype "passive"))
      (node (ref "IC1") (pin "3") (pinfunction "C2-_3") (pintype "bidirectional"))
    )
    (net (code "25") (name "Net-(IC1-SHDN)") (class "Default")
      (node (ref "IC1") (pin "8") (pinfunction "SHDN_8") (pintype "bidirectional"))
      (node (ref "R2") (pin "1") (pinfunction "1_1") (pintype "passive"))
    )
    (net (code "26") (name "Net-(IC3-OSC0)") (class "Default")
      (node (ref "C11") (pin "2") (pinfunction "2_2") (pintype "passive"))
      (node (ref "IC3") (pin "88") (pinfunction "OSC0_88") (pintype "bidirectional"))
      (node (ref "X2") (pin "1") (pinfunction "1_1") (pintype "bidirectional"))
    )
    (net (code "27") (name "Net-(IC3-OSC1)") (class "Default")
      (node (ref "C8") (pin "2") (pinfunction "2_2") (pintype "passive"))
      (node (ref "IC3") (pin "89") (pinfunction "OSC1_89") (pintype "bidirectional"))
      (node (ref "X2") (pin "3") (pinfunction "2_3") (pintype "bidirectional"))
    )
    (net (code "28") (name "Net-(IC3-RBIAS)") (class "Default")
      (node (ref "IC3") (pin "59") (pinfunction "RBIAS_59") (pintype "bidirectional"))
      (node (ref "R13") (pin "2") (pinfunction "2_2") (pintype "passive"))
    )
    (net (code "29") (name "Net-(IC3-VBAT)") (class "Default")
      (node (ref "C25") (pin "1") (pinfunction "1_1") (pintype "passive"))
      (node (ref "IC3") (pin "68") (pinfunction "VBAT_68") (pintype "bidirectional"))
      (node (ref "R10") (pin "1") (pinfunction "1_1") (pintype "passive"))
    )
    (net (code "30") (name "Net-(IC3-XOSC0)") (class "Default")
      (node (ref "C15") (pin "2") (pinfunction "2_2") (pintype "passive"))
      (node (ref "IC3") (pin "66") (pinfunction "XOSC0_66") (pintype "bidirectional"))
      (node (ref "X1") (pin "P$2") (pinfunction "2_P$2") (pintype "bidirectional"))
    )
    (net (code "31") (name "Net-(IC3-XOSC1)") (class "Default")
      (node (ref "C14") (pin "2") (pinfunction "2_2") (pintype "passive"))
      (node (ref "IC3") (pin "67") (pinfunction "XOSC1_67") (pintype "bidirectional"))
      (node (ref "X1") (pin "P$1") (pinfunction "1_P$1") (pintype "bidirectional"))
    )
    (net (code "32") (name "Net-(IC5-CBUS2)") (class "Default")
      (node (ref "IC5") (pin "5") (pinfunction "CBUS2_5") (pintype "bidirectional"))
      (node (ref "R76") (pin "1") (pinfunction "1_1") (pintype "passive"))
    )
    (net (code "33") (name "Net-(IC5-USBDM)") (class "Default")
      (node (ref "IC5") (pin "7") (pinfunction "USBDM_7") (pintype "bidirectional"))
      (node (ref "R75") (pin "1") (pinfunction "1_1") (pintype "passive"))
    )
    (net (code "34") (name "Net-(IC5-USBDP)") (class "Default")
      (node (ref "IC5") (pin "6") (pinfunction "USBDP_6") (pintype "bidirectional"))
      (node (ref "R74") (pin "1") (pinfunction "1_1") (pintype "passive"))
    )
    (net (code "35") (name "Net-(IC5-VCC)") (class "Default")
      (node (ref "C92") (pin "1") (pinfunction "1_1") (pintype "passive"))
      (node (ref "IC5") (pin "10") (pinfunction "VCC_10") (pintype "bidirectional"))
      (node (ref "L1") (pin "2") (pinfunction "2_2") (pintype "passive"))
    )
    (net (code "36") (name "Net-(J1-D+)") (class "Default")
      (node (ref "C91") (pin "1") (pinfunction "1_1") (pintype "passive"))
      (node (ref "D23") (pin "1") (pinfunction "1_1") (pintype "bidirectional"))
      (node (ref "J1") (pin "3") (pinfunction "D+_3") (pintype "bidirectional"))
      (node (ref "R74") (pin "2") (pinfunction "2_2") (pintype "passive"))
    )
    (net (code "37") (name "Net-(J1-D-)") (class "Default")
      (node (ref "C90") (pin "1") (pinfunction "1_1") (pintype "passive"))
      (node (ref "D23") (pin "2") (pinfunction "2_2") (pintype "bidirectional"))
      (node (ref "J1") (pin "2") (pinfunction "D-_2") (pintype "bidirectional"))
      (node (ref "R75") (pin "2") (pinfunction "2_2") (pintype "passive"))
    )
    (net (code "38") (name "Net-(J2-Pad7)") (class "Default")
      (node (ref "J2") (pin "7") (pinfunction "7_7") (pintype "bidirectional"))
      (node (ref "R5") (pin "2") (pinfunction "2_2") (pintype "passive"))
    )
    (net (code "39") (name "Net-(LD1-PadC)") (class "Default")
      (node (ref "LD1") (pin "C") (pinfunction "C_C") (pintype "passive"))
      (node (ref "R76") (pin "2") (pinfunction "2_2") (pintype "passive"))
    )
    (net (code "40") (name "Net-(LD2-PadA)") (class "Default")
      (node (ref "LD2") (pin "A") (pinfunction "A_A") (pintype "passive"))
      (node (ref "R6") (pin "1") (pinfunction "1_1") (pintype "passive"))
    )
    (net (code "41") (name "Net-(LD3-PadA)") (class "Default")
      (node (ref "LD3") (pin "A") (pinfunction "A_A") (pintype "passive"))
      (node (ref "R7") (pin "1") (pinfunction "1_1") (pintype "passive"))
    )
    (net (code "42") (name "Net-(T1-E)") (class "Default")
      (node (ref "C31") (pin "2") (pinfunction "2_2") (pintype "passive"))
      (node (ref "R33") (pin "1") (pinfunction "1_1") (pintype "passive"))
      (node (ref "T1") (pin "2") (pinfunction "E_2") (pintype "passive"))
    )
    (net (code "43") (name "Net-(T2-B)") (class "Default")
      (node (ref "C31") (pin "1") (pinfunction "1_1") (pintype "passive"))
      (node (ref "R34") (pin "2") (pinfunction "2_2") (pintype "passive"))
      (node (ref "T2") (pin "1") (pinfunction "B_1") (pintype "passive"))
    )
    (net (code "44") (name "Net-(T2-C)") (class "Default")
      (node (ref "C30") (pin "2") (pinfunction "2_2") (pintype "passive"))
      (node (ref "R34") (pin "1") (pinfunction "1_1") (pintype "passive"))
      (node (ref "R35") (pin "2") (pinfunction "2_2") (pintype "passive"))
      (node (ref "T2") (pin "3") (pinfunction "C_3") (pintype "passive"))
    )
    (net (code "45") (name "Net-(T3-B)") (class "Default")
      (node (ref "R12") (pin "1") (pinfunction "1_1") (pintype "passive"))
      (node (ref "R8") (pin "2") (pinfunction "2_2") (pintype "passive"))
      (node (ref "T3") (pin "1") (pinfunction "B_1") (pintype "passive"))
    )
    (net (code "46") (name "SCL") (class "Default")
      (node (ref "IC2") (pin "6") (pinfunction "SCL_6") (pintype "bidirectional"))
      (node (ref "IC3") (pin "37") (pinfunction "PA4_37") (pintype "bidirectional"))
      (node (ref "R4") (pin "2") (pinfunction "2_2") (pintype "passive"))
    )
    (net (code "47") (name "SDA") (class "Default")
      (node (ref "IC2") (pin "5") (pinfunction "SDA_5") (pintype "bidirectional"))
      (node (ref "IC3") (pin "38") (pinfunction "PA5_38") (pintype "bidirectional"))
      (node (ref "R1") (pin "2") (pinfunction "2_2") (pintype "passive"))
    )
    (net (code "48") (name "SWCLK") (class "Default")
      (node (ref "IC3") (pin "100") (pinfunction "PC0/TCK/SWCLK_100") (pintype "bidirectional"))
      (node (ref "J2") (pin "3") (pinfunction "3_3") (pintype "bidirectional"))
    )
    (net (code "49") (name "SWDIO") (class "Default")
      (node (ref "IC3") (pin "99") (pinfunction "PC1/TMS/SWDIO_99") (pintype "bidirectional"))
      (node (ref "J2") (pin "5") (pinfunction "5_5") (pintype "bidirectional"))
    )
    (net (code "50") (name "TDI") (class "Default")
      (node (ref "IC3") (pin "98") (pinfunction "PC2/TDI_98") (pintype "bidirectional"))
      (node (ref "J2") (pin "6") (pinfunction "6_6") (pintype "bidirectional"))
    )
    (net (code "51") (name "TDO") (class "Default")
      (node (ref "IC3") (pin "97") (pinfunction "PC3/TDO/SWO_97") (pintype "bidirectional"))
      (node (ref "J2") (pin "8") (pinfunction "8_8") (pintype "bidirectional"))
    )
    (net (code "52") (name "UNPLUGGED") (class "Default")
      (node (ref "IC3") (pin "64") (pinfunction "~{WAKE}_64") (pintype "bidirectional"))
      (node (ref "IC3") (pin "72") (pinfunction "PM6_72") (pintype "bidirectional"))
      (node (ref "R9") (pin "2") (pinfunction "2_2") (pintype "passive"))
      (node (ref "T3") (pin "3") (pinfunction "C_3") (pintype "passive"))
    )
    (net (code "53") (name "USB_SLEEP#") (class "Default")
      (node (ref "IC3") (pin "50") (pinfunction "PG1_50") (pintype "bidirectional"))
      (node (ref "IC5") (pin "14") (pinfunction "CBUS3_14") (pintype "bidirectional"))
    )
    (net (code "54") (name "VBUS_SENSE") (class "Default")
      (node (ref "IC3") (pin "21") (pinfunction "PK3_21") (pintype "bidirectional"))
      (node (ref "IC3") (pin "22") (pinfunction "PC7_22") (pintype "bidirectional"))
      (node (ref "IC3") (pin "23") (pinfunction "PC6_23") (pintype "bidirectional"))
      (node (ref "R11") (pin "2") (pinfunction "2_2") (pintype "passive"))
      (node (ref "R8") (pin "1") (pinfunction "1_1") (pintype "passive"))
    )
    (net (code "55") (name "VDDC") (class "Default")
      (node (ref "C10") (pin "1") (pinfunction "1_1") (pintype "passive"))
      (node (ref "C17") (pin "1") (pinfunction "1_1") (pintype "passive"))
      (node (ref "IC3") (pin "115") (pinfunction "VDDC2_115") (pintype "bidirectional"))
      (node (ref "IC3") (pin "87") (pinfunction "VDDC1_87") (pintype "bidirectional"))
    )
    (net (code "56") (name "unconnected-(IC3-EN0RXIN-Pad53)") (class "Default")
      (node (ref "IC3") (pin "53") (pinfunction "EN0RXIN_53") (pintype "bidirectional"))
    )
    (net (code "57") (name "unconnected-(IC3-EN0RXIP-Pad54)") (class "Default")
      (node (ref "IC3") (pin "54") (pinfunction "EN0RXIP_54") (pintype "bidirectional"))
    )
    (net (code "58") (name "unconnected-(IC3-EN0TXON-Pad56)") (class "Default")
      (node (ref "IC3") (pin "56") (pinfunction "EN0TXON_56") (pintype "bidirectional"))
    )
    (net (code "59") (name "unconnected-(IC3-EN0TXOP-Pad57)") (class "Default")
      (node (ref "IC3") (pin "57") (pinfunction "EN0TXOP_57") (pintype "bidirectional"))
    )
    (net (code "60") (name "unconnected-(IC3-PA3-Pad36)") (class "Default")
      (node (ref "IC3") (pin "36") (pinfunction "PA3_36") (pintype "bidirectional"))
    )
    (net (code "61") (name "unconnected-(IC3-PB0-Pad95)") (class "Default")
      (node (ref "IC3") (pin "95") (pinfunction "PB0_95") (pintype "bidirectional"))
    )
    (net (code "62") (name "unconnected-(IC3-PB1-Pad96)") (class "Default")
      (node (ref "IC3") (pin "96") (pinfunction "PB1_96") (pintype "bidirectional"))
    )
    (net (code "63") (name "unconnected-(IC3-PB2-Pad91)") (class "Default")
      (node (ref "IC3") (pin "91") (pinfunction "PB2_91") (pintype "bidirectional"))
    )
    (net (code "64") (name "unconnected-(IC3-PB3-Pad92)") (class "Default")
      (node (ref "IC3") (pin "92") (pinfunction "PB3_92") (pintype "bidirectional"))
    )
    (net (code "65") (name "unconnected-(IC3-PB4-Pad121)") (class "Default")
      (node (ref "IC3") (pin "121") (pinfunction "PB4_121") (pintype "bidirectional"))
    )
    (net (code "66") (name "unconnected-(IC3-PB5-Pad120)") (class "Default")
      (node (ref "IC3") (pin "120") (pinfunction "PB5_120") (pintype "bidirectional"))
    )
    (net (code "67") (name "unconnected-(IC3-PC4-Pad25)") (class "Default")
      (node (ref "IC3") (pin "25") (pinfunction "PC4_25") (pintype "bidirectional"))
    )
    (net (code "68") (name "unconnected-(IC3-PD0-Pad1)") (class "Default")
      (node (ref "IC3") (pin "1") (pinfunction "PD0_1") (pintype "bidirectional"))
    )
    (net (code "69") (name "unconnected-(IC3-PD1-Pad2)") (class "Default")
      (node (ref "IC3") (pin "2") (pinfunction "PD1_2") (pintype "bidirectional"))
    )
    (net (code "70") (name "unconnected-(IC3-PD2-Pad3)") (class "Default")
      (node (ref "IC3") (pin "3") (pinfunction "PD2_3") (pintype "bidirectional"))
    )
    (net (code "71") (name "unconnected-(IC3-PD3-Pad4)") (class "Default")
      (node (ref "IC3") (pin "4") (pinfunction "PD3_4") (pintype "bidirectional"))
    )
    (net (code "72") (name "unconnected-(IC3-PD4-Pad125)") (class "Default")
      (node (ref "IC3") (pin "125") (pinfunction "PD4_125") (pintype "bidirectional"))
    )
    (net (code "73") (name "unconnected-(IC3-PD5-Pad126)") (class "Default")
      (node (ref "IC3") (pin "126") (pinfunction "PD5_126") (pintype "bidirectional"))
    )
    (net (code "74") (name "unconnected-(IC3-PD6-Pad127)") (class "Default")
      (node (ref "IC3") (pin "127") (pinfunction "PD6_127") (pintype "bidirectional"))
    )
    (net (code "75") (name "unconnected-(IC3-PD7-Pad128)") (class "Default")
      (node (ref "IC3") (pin "128") (pinfunction "PD7_128") (pintype "bidirectional"))
    )
    (net (code "76") (name "unconnected-(IC3-PE0-Pad15)") (class "Default")
      (node (ref "IC3") (pin "15") (pinfunction "PE0_15") (pintype "bidirectional"))
    )
    (net (code "77") (name "unconnected-(IC3-PE1-Pad14)") (class "Default")
      (node (ref "IC3") (pin "14") (pinfunction "PE1_14") (pintype "bidirectional"))
    )
    (net (code "78") (name "unconnected-(IC3-PE2-Pad13)") (class "Default")
      (node (ref "IC3") (pin "13") (pinfunction "PE2_13") (pintype "bidirectional"))
    )
    (net (code "79") (name "unconnected-(IC3-PE4-Pad123)") (class "Default")
      (node (ref "IC3") (pin "123") (pinfunction "PE4_123") (pintype "bidirectional"))
    )
    (net (code "80") (name "unconnected-(IC3-PE5-Pad124)") (class "Default")
      (node (ref "IC3") (pin "124") (pinfunction "PE5_124") (pintype "bidirectional"))
    )
    (net (code "81") (name "unconnected-(IC3-PF0-Pad42)") (class "Default")
      (node (ref "IC3") (pin "42") (pinfunction "PF0_42") (pintype "bidirectional"))
    )
    (net (code "82") (name "unconnected-(IC3-PF1-Pad43)") (class "Default")
      (node (ref "IC3") (pin "43") (pinfunction "PF1_43") (pintype "bidirectional"))
    )
    (net (code "83") (name "unconnected-(IC3-PF2-Pad44)") (class "Default")
      (node (ref "IC3") (pin "44") (pinfunction "PF2_44") (pintype "bidirectional"))
    )
    (net (code "84") (name "unconnected-(IC3-PF3-Pad45)") (class "Default")
      (node (ref "IC3") (pin "45") (pinfunction "PF3_45") (pintype "bidirectional"))
    )
    (net (code "85") (name "unconnected-(IC3-PG0-Pad49)") (class "Default")
      (node (ref "IC3") (pin "49") (pinfunction "PG0_49") (pintype "bidirectional"))
    )
    (net (code "86") (name "unconnected-(IC3-PH2-Pad31)") (class "Default")
      (node (ref "IC3") (pin "31") (pinfunction "PH2_31") (pintype "bidirectional"))
    )
    (net (code "87") (name "unconnected-(IC3-PH3-Pad32)") (class "Default")
      (node (ref "IC3") (pin "32") (pinfunction "PH3_32") (pintype "bidirectional"))
    )
    (net (code "88") (name "unconnected-(IC3-PJ0-Pad116)") (class "Default")
      (node (ref "IC3") (pin "116") (pinfunction "PJ0_116") (pintype "bidirectional"))
    )
    (net (code "89") (name "unconnected-(IC3-PJ1-Pad117)") (class "Default")
      (node (ref "IC3") (pin "117") (pinfunction "PJ1_117") (pintype "bidirectional"))
    )
    (net (code "90") (name "unconnected-(IC3-PK0-Pad18)") (class "Default")
      (node (ref "IC3") (pin "18") (pinfunction "PK0_18") (pintype "bidirectional"))
    )
    (net (code "91") (name "unconnected-(IC3-PK1-Pad19)") (class "Default")
      (node (ref "IC3") (pin "19") (pinfunction "PK1_19") (pintype "bidirectional"))
    )
    (net (code "92") (name "unconnected-(IC3-PK2-Pad20)") (class "Default")
      (node (ref "IC3") (pin "20") (pinfunction "PK2_20") (pintype "bidirectional"))
    )
    (net (code "93") (name "unconnected-(IC3-PL0-Pad81)") (class "Default")
      (node (ref "IC3") (pin "81") (pinfunction "PL0_81") (pintype "bidirectional"))
    )
    (net (code "94") (name "unconnected-(IC3-PL1-Pad82)") (class "Default")
      (node (ref "IC3") (pin "82") (pinfunction "PL1_82") (pintype "bidirectional"))
    )
    (net (code "95") (name "unconnected-(IC3-PL2-Pad83)") (class "Default")
      (node (ref "IC3") (pin "83") (pinfunction "PL2_83") (pintype "bidirectional"))
    )
    (net (code "96") (name "unconnected-(IC3-PL3-Pad84)") (class "Default")
      (node (ref "IC3") (pin "84") (pinfunction "PL3_84") (pintype "bidirectional"))
    )
    (net (code "97") (name "unconnected-(IC3-PL4-Pad85)") (class "Default")
      (node (ref "IC3") (pin "85") (pinfunction "PL4_85") (pintype "bidirectional"))
    )
    (net (code "98") (name "unconnected-(IC3-PL5-Pad86)") (class "Default")
      (node (ref "IC3") (pin "86") (pinfunction "PL5_86") (pintype "bidirectional"))
    )
    (net (code "99") (name "unconnected-(IC3-PL6-Pad94)") (class "Default")
      (node (ref "IC3") (pin "94") (pinfunction "PL6_94") (pintype "bidirectional"))
    )
    (net (code "100") (name "unconnected-(IC3-PL7-Pad93)") (class "Default")
      (node (ref "IC3") (pin "93") (pinfunction "PL7_93") (pintype "bidirectional"))
    )
    (net (code "101") (name "unconnected-(IC3-PM0-Pad78)") (class "Default")
      (node (ref "IC3") (pin "78") (pinfunction "PM0_78") (pintype "bidirectional"))
    )
    (net (code "102") (name "unconnected-(IC3-PM1-Pad77)") (class "Default")
      (node (ref "IC3") (pin "77") (pinfunction "PM1_77") (pintype "bidirectional"))
    )
    (net (code "103") (name "unconnected-(IC3-PM2-Pad76)") (class "Default")
      (node (ref "IC3") (pin "76") (pinfunction "PM2_76") (pintype "bidirectional"))
    )
    (net (code "104") (name "unconnected-(IC3-PM3-Pad75)") (class "Default")
      (node (ref "IC3") (pin "75") (pinfunction "PM3_75") (pintype "bidirectional"))
    )
    (net (code "105") (name "unconnected-(IC3-PM7-Pad71)") (class "Default")
      (node (ref "IC3") (pin "71") (pinfunction "PM7_71") (pintype "bidirectional"))
    )
    (net (code "106") (name "unconnected-(IC3-PN0-Pad107)") (class "Default")
      (node (ref "IC3") (pin "107") (pinfunction "PN0_107") (pintype "bidirectional"))
    )
    (net (code "107") (name "unconnected-(IC3-PN1-Pad108)") (class "Default")
      (node (ref "IC3") (pin "108") (pinfunction "PN1_108") (pintype "bidirectional"))
    )
    (net (code "108") (name "unconnected-(IC3-PN2-Pad109)") (class "Default")
      (node (ref "IC3") (pin "109") (pinfunction "PN2_109") (pintype "bidirectional"))
    )
    (net (code "109") (name "unconnected-(IC3-PN3-Pad110)") (class "Default")
      (node (ref "IC3") (pin "110") (pinfunction "PN3_110") (pintype "bidirectional"))
    )
    (net (code "110") (name "unconnected-(IC3-PN4-Pad111)") (class "Default")
      (node (ref "IC3") (pin "111") (pinfunction "PN4_111") (pintype "bidirectional"))
    )
    (net (code "111") (name "unconnected-(IC3-PN5-Pad112)") (class "Default")
      (node (ref "IC3") (pin "112") (pinfunction "PN5_112") (pintype "bidirectional"))
    )
    (net (code "112") (name "unconnected-(IC3-PP0-Pad118)") (class "Default")
      (node (ref "IC3") (pin "118") (pinfunction "PP0_118") (pintype "bidirectional"))
    )
    (net (code "113") (name "unconnected-(IC3-PP1-Pad119)") (class "Default")
      (node (ref "IC3") (pin "119") (pinfunction "PP1_119") (pintype "bidirectional"))
    )
    (net (code "114") (name "unconnected-(IC3-PP2-Pad103)") (class "Default")
      (node (ref "IC3") (pin "103") (pinfunction "PP2_103") (pintype "bidirectional"))
    )
    (net (code "115") (name "unconnected-(IC3-PP3-Pad104)") (class "Default")
      (node (ref "IC3") (pin "104") (pinfunction "PP3_104") (pintype "bidirectional"))
    )
    (net (code "116") (name "unconnected-(IC3-PP4-Pad105)") (class "Default")
      (node (ref "IC3") (pin "105") (pinfunction "PP4_105") (pintype "bidirectional"))
    )
    (net (code "117") (name "unconnected-(IC3-PP5-Pad106)") (class "Default")
      (node (ref "IC3") (pin "106") (pinfunction "PP5_106") (pintype "bidirectional"))
    )
    (net (code "118") (name "unconnected-(IC3-PQ0-Pad5)") (class "Default")
      (node (ref "IC3") (pin "5") (pinfunction "PQ0_5") (pintype "bidirectional"))
    )
    (net (code "119") (name "unconnected-(IC3-PQ1-Pad6)") (class "Default")
      (node (ref "IC3") (pin "6") (pinfunction "PQ1_6") (pintype "bidirectional"))
    )
    (net (code "120") (name "unconnected-(IC3-PQ2-Pad11)") (class "Default")
      (node (ref "IC3") (pin "11") (pinfunction "PQ2_11") (pintype "bidirectional"))
    )
    (net (code "121") (name "unconnected-(IC3-PQ3-Pad27)") (class "Default")
      (node (ref "IC3") (pin "27") (pinfunction "PQ3_27") (pintype "bidirectional"))
    )
    (net (code "122") (name "unconnected-(IC3-PQ4-Pad102)") (class "Default")
      (node (ref "IC3") (pin "102") (pinfunction "PQ4_102") (pintype "bidirectional"))
    )
    (net (code "123") (name "unconnected-(IC3-VDD11-Pad90)") (class "Default")
      (node (ref "IC3") (pin "90") (pinfunction "VDD11_90") (pintype "bidirectional"))
    )
    (net (code "124") (name "unconnected-(IC3-~{HIB}-Pad65)") (class "Default")
      (node (ref "IC3") (pin "65") (pinfunction "~{HIB}_65") (pintype "bidirectional"))
    )
    (net (code "125") (name "unconnected-(T1-C-Pad3)") (class "Default")
      (node (ref "T1") (pin "3") (pinfunction "C_3") (pintype "passive"))
    )
    (net (code "126") (name "~{RST}") (class "Default")
      (node (ref "IC3") (pin "70") (pinfunction "~{RST}_70") (pintype "bidirectional"))
      (node (ref "J2") (pin "9") (pinfunction "9_9") (pintype "bidirectional"))
      (node (ref "R14") (pin "1") (pinfunction "1_1") (pintype "passive"))
    )
  )
)
